# 1.net
KiCad netlist of a schematic drawn in Altium Designer
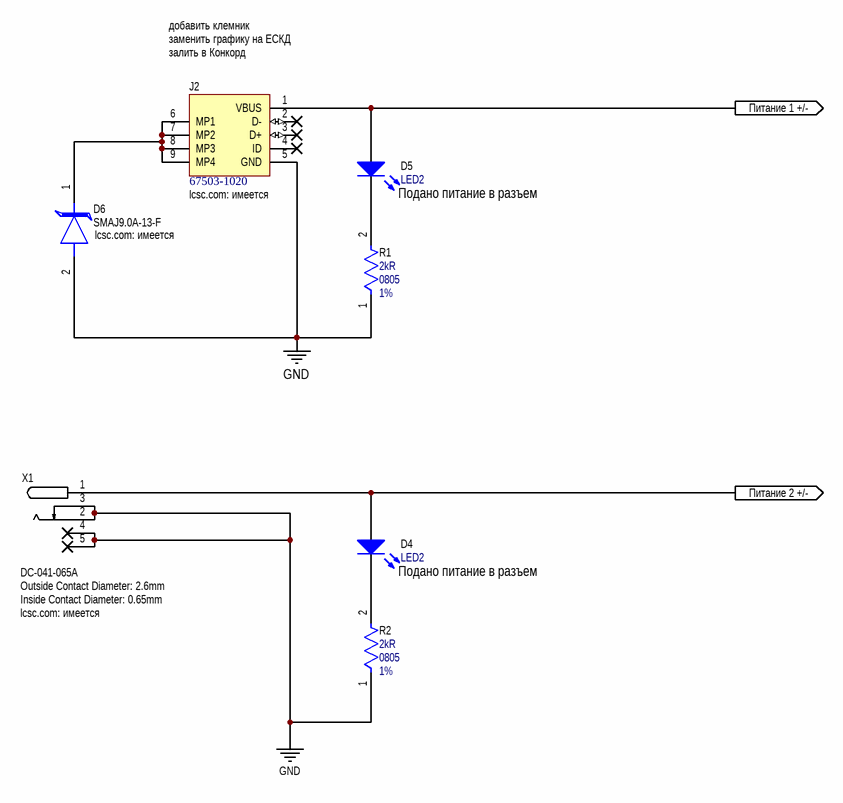
[diagram p0: Блок1.SchDoc]

(export (version "E")
  (design (tool "Eeschema 10.0.6"))
  (components
    (comp (ref "D4")
      (value "LED2")
      (footprint "3.2X1.6X1.1")
      (description "Typical RED, GREEN, YELLOW, AMBER GaAs LED")
      (fields
        (field (name "PARAMETER 1") "Подано питание в разъем")
        (field (name "PUBLISHER") "Altium Limited")
      )
      (libsource (lib "Miscellaneous Devices") (part "LED2"))
    )
    (comp (ref "D5")
      (value "LED2")
      (footprint "3.2X1.6X1.1")
      (description "Typical RED, GREEN, YELLOW, AMBER GaAs LED")
      (fields
        (field (name "PARAMETER 1") "Подано питание в разъем")
        (field (name "PUBLISHER") "Altium Limited")
      )
      (libsource (lib "Miscellaneous Devices") (part "LED2"))
    )
    (comp (ref "D6")
      (value "SMAJ9.0A-13-F")
      (footprint "FP-SMA-MFG")
      (description "TVS DIODE 9V 15.4V SMA")
      (fields
        (field (name "OCTOPART") "https://octopart.com/smaj9.0a-13-f-diodes+inc.-350369")
        (field (name "MANUFACTURER") "Diodes Inc")
        (field (name "LCSC.COM") "имеется")
      )
      (libsource (lib "Altium Content Vault") (part "e2a1dd67f652bf44a5c14c718bbe709"))
    )
    (comp (ref "J2")
      (value "67503-1020")
      (footprint "MOLX-67503-1020_V")
      (description "USB, MINI, SMD, RA KME04-USBMU03A01")
      (fields (field (name "MANUFACTURER") "Molex") (field (name "LCSC.COM") "имеется"))
      (libsource (lib "Altium Content Vault") (part "MOLX-67503-1020"))
    )
    (comp (ref "R1")
      (value "MC01W0805110K")
      (footprint "FP-MC01W0805-IPC_C")
      (description "Resistor, 10K, 0.1W, 1%, 0805, Reel")
      (fields
        (field (name "RESISTANCE") "2kR")
        (field (name "CASE/PACKAGE") "0805")
        (field (name "TOLERANCE") "1%")
        (field (name "MANUFACTURER") "Multicomp")
      )
      (libsource (lib "Altium Content Vault") (part "1029c3af85768c4190bb7ad29bc67b5"))
    )
    (comp (ref "R2")
      (value "MC01W0805110K")
      (footprint "FP-MC01W0805-IPC_C")
      (description "Resistor, 10K, 0.1W, 1%, 0805, Reel")
      (fields
        (field (name "RESISTANCE") "2kR")
        (field (name "CASE/PACKAGE") "0805")
        (field (name "TOLERANCE") "1%")
        (field (name "MANUFACTURER") "Multicomp")
      )
      (libsource (lib "Altium Content Vault") (part "1029c3af85768c4190bb7ad29bc67b5"))
    )
    (comp (ref "X1")
      (value "DC-041-065A")
      (footprint "DC-041-065A")
      (description "Surface Mount DC Power Receptacle 0.65mm -20℃~+70℃ 2.6mm 500mA 30V SMD AC/DC Power Connectors ROHS")
      (fields
        (field (name "BOM_SUPPLIER PART") "C192728")
        (field (name "INSIDE CONTACT DIAMETER") "0.65mm")
        (field (name "OUTSIDE CONTACT DIAMETER") "2.6mm")
        (field (name "LCSC.COM") "имеется")
        (field (name "CONTRIBUTOR") "LCSC")
      )
      (libsource (lib "lcsc") (part "DC-041-065A"))
    )
  )
  (nets
    (net (code "1") (name "/Питание 1 +{slash}-") (class "Default")
      (node (ref "D5") (pin "1") (pinfunction "A_1") (pintype "passive"))
      (node (ref "J2") (pin "1") (pinfunction "VBUS_1") (pintype "power_in"))
    )
    (net (code "2") (name "/Питание 2 +{slash}-") (class "Default")
      (node (ref "D4") (pin "1") (pinfunction "A_1") (pintype "passive"))
      (node (ref "X1") (pin "1") (pinfunction "1_1") (pintype "passive"))
    )
    (net (code "3") (name "GND") (class "Default")
      (node (ref "D6") (pin "2") (pinfunction "A_2") (pintype "passive"))
      (node (ref "J2") (pin "5") (pinfunction "GND_5") (pintype "power_in"))
      (node (ref "R1") (pin "1") (pinfunction "1_1") (pintype "passive"))
      (node (ref "R2") (pin "1") (pinfunction "1_1") (pintype "passive"))
      (node (ref "X1") (pin "2") (pinfunction "2_2") (pintype "passive"))
      (node (ref "X1") (pin "3") (pinfunction "3_3") (pintype "passive"))
      (node (ref "X1") (pin "4") (pinfunction "4_4") (pintype "passive"))
      (node (ref "X1") (pin "5") (pinfunction "5_5") (pintype "passive"))
    )
    (net (code "4") (name "Net-(D4-K)") (class "Default")
      (node (ref "D4") (pin "2") (pinfunction "K_2") (pintype "passive"))
      (node (ref "R2") (pin "2") (pinfunction "2_2") (pintype "passive"))
    )
    (net (code "5") (name "Net-(D5-K)") (class "Default")
      (node (ref "D5") (pin "2") (pinfunction "K_2") (pintype "passive"))
      (node (ref "R1") (pin "2") (pinfunction "2_2") (pintype "passive"))
    )
    (net (code "6") (name "Net-(D6-C)") (class "Default")
      (node (ref "D6") (pin "1") (pinfunction "C_1") (pintype "passive"))
      (node (ref "J2") (pin "6") (pinfunction "MP1_6") (pintype "passive"))
      (node (ref "J2") (pin "7") (pinfunction "MP2_7") (pintype "passive"))
      (node (ref "J2") (pin "8") (pinfunction "MP3_8") (pintype "passive"))
      (node (ref "J2") (pin "9") (pinfunction "MP4_9") (pintype "passive"))
    )
    (net (code "7") (name "unconnected-(J2-D+-Pad3)") (class "Default")
      (node (ref "J2") (pin "3") (pinfunction "D+_3") (pintype "bidirectional+no_connect"))
    )
    (net (code "8") (name "unconnected-(J2-D--Pad2)") (class "Default")
      (node (ref "J2") (pin "2") (pinfunction "D-_2") (pintype "bidirectional+no_connect"))
    )
    (net (code "9") (name "unconnected-(J2-ID-Pad4)") (class "Default")
      (node (ref "J2") (pin "4") (pinfunction "ID_4") (pintype "passive+no_connect"))
    )
  )
)
